# tiny10_basic.net
KiCad netlist of a schematic drawn in EAGLE
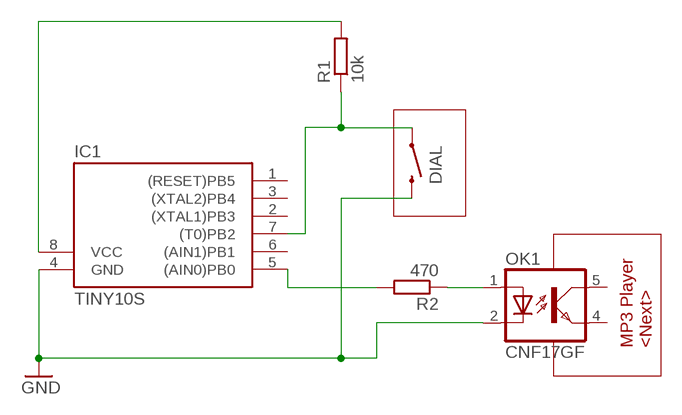
[diagram p0: schematic, sheet 1]

(export (version "E")
  (design (tool "Eeschema 10.0.6"))
  (components
    (comp (ref "DIAL")
      (value "SWITCH-MOMENTARY-2PTH")
      (footprint "eagle-import:TACTILE-PTH")
      (libsource (lib "eagle-import") (part "SWITCH-MOMENTARY-2PTH"))
    )
    (comp (ref "IC1")
      (value "TINY10S")
      (footprint "eagle-import:SOIC8")
      (libsource (lib "eagle-import") (part "TINY10S"))
    )
    (comp (ref "OK1")
      (value "CNF17GF")
      (footprint "eagle-import:DIL06B")
      (libsource (lib "eagle-import") (part "CNF17GF"))
    )
    (comp (ref "R1")
      (value "10k")
      (footprint "eagle-import:0204V")
      (libsource (lib "eagle-import") (part "R-EU_0204/2V"))
    )
    (comp (ref "R2")
      (value "470")
      (footprint "eagle-import:0204V")
      (libsource (lib "eagle-import") (part "R-EU_0204/2V"))
    )
  )
  (nets
    (net (code "1") (name "GND") (class "Default")
      (node (ref "DIAL") (pin "3") (pinfunction "2_3") (pintype "passive"))
      (node (ref "IC1") (pin "4") (pinfunction "GND_4") (pintype "power_in"))
      (node (ref "OK1") (pin "2") (pinfunction "C_2") (pintype "passive"))
    )
    (net (code "2") (name "Net-(IC1-(AIN0)PB0)") (class "Default")
      (node (ref "IC1") (pin "5") (pinfunction "(AIN0)PB0_5") (pintype "bidirectional"))
      (node (ref "R2") (pin "2") (pinfunction "2_2") (pintype "passive"))
    )
    (net (code "3") (name "Net-(IC1-(T0)PB2)") (class "Default")
      (node (ref "DIAL") (pin "1") (pinfunction "1_1") (pintype "passive"))
      (node (ref "IC1") (pin "7") (pinfunction "(T0)PB2_7") (pintype "bidirectional"))
      (node (ref "R1") (pin "1") (pinfunction "1_1") (pintype "passive"))
    )
    (net (code "4") (name "Net-(IC1-VCC)") (class "Default")
      (node (ref "IC1") (pin "8") (pinfunction "VCC_8") (pintype "power_in"))
      (node (ref "R1") (pin "2") (pinfunction "2_2") (pintype "passive"))
    )
    (net (code "5") (name "Net-(OK1-A)") (class "Default")
      (node (ref "OK1") (pin "1") (pinfunction "A_1") (pintype "passive"))
      (node (ref "R2") (pin "1") (pinfunction "1_1") (pintype "passive"))
    )
    (net (code "6") (name "unconnected-(IC1-(AIN1)PB1-Pad6)") (class "Default")
      (node (ref "IC1") (pin "6") (pinfunction "(AIN1)PB1_6") (pintype "bidirectional"))
    )
    (net (code "7") (name "unconnected-(IC1-(RESET)PB5-Pad1)") (class "Default")
      (node (ref "IC1") (pin "1") (pinfunction "(RESET)PB5_1") (pintype "bidirectional"))
    )
    (net (code "8") (name "unconnected-(IC1-(XTAL1)PB3-Pad2)") (class "Default")
      (node (ref "IC1") (pin "2") (pinfunction "(XTAL1)PB3_2") (pintype "bidirectional"))
    )
    (net (code "9") (name "unconnected-(IC1-(XTAL2)PB4-Pad3)") (class "Default")
      (node (ref "IC1") (pin "3") (pinfunction "(XTAL2)PB4_3") (pintype "bidirectional"))
    )
    (net (code "10") (name "unconnected-(OK1-COL-Pad5)") (class "Default")
      (node (ref "OK1") (pin "5") (pinfunction "COL_5") (pintype "passive"))
    )
    (net (code "11") (name "unconnected-(OK1-EMIT-Pad4)") (class "Default")
      (node (ref "OK1") (pin "4") (pinfunction "EMIT_4") (pintype "passive"))
    )
  )
)
